# Tugas_Day_0-_Qurrata_Choir_Marham.net
KiCad netlist of a schematic drawn in EAGLE
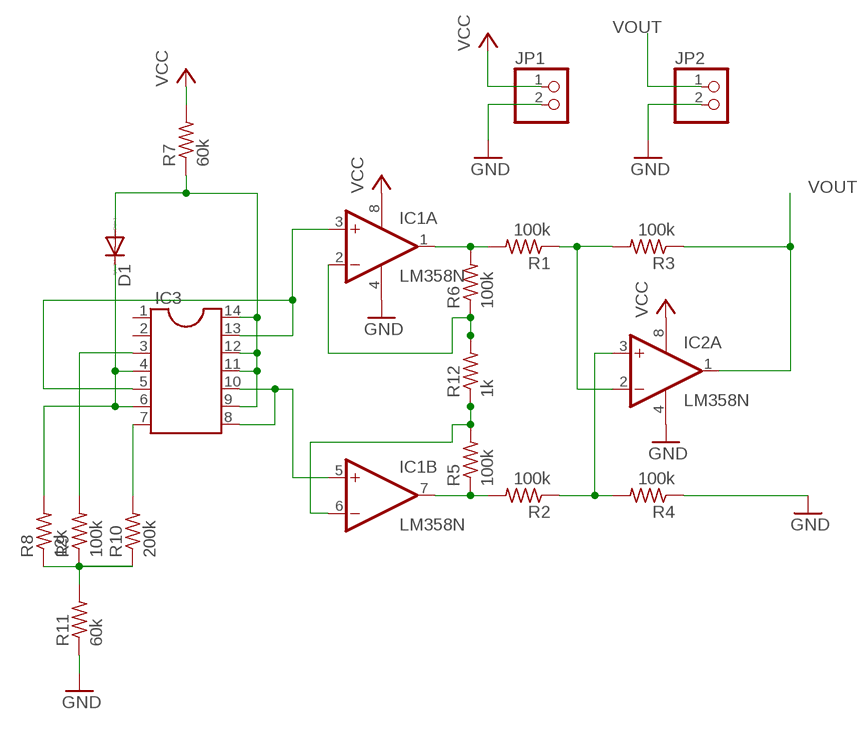
[diagram p0: schematic, sheet 1]

(export (version "E")
  (design (tool "Eeschema 10.0.6"))
  (components
    (comp (ref "D1")
      (value "DIODE-D-7.5")
      (footprint "eagle-import:D-7.5")
      (libsource (lib "eagle-import") (part "DIODE-D-7.5"))
    )
    (comp (ref "IC1")
      (value "LM358N")
      (footprint "eagle-import:DIL08")
      (libsource (lib "eagle-import") (part "LM358N"))
    )
    (comp (ref "IC2")
      (value "LM358N")
      (footprint "eagle-import:DIL08")
      (libsource (lib "eagle-import") (part "LM358N"))
    )
    (comp (ref "IC3")
      (value "DIL14")
      (footprint "eagle-import:DIL14")
      (libsource (lib "eagle-import") (part "DIL14"))
    )
    (comp (ref "JP1")
      (value "PINHD-1X2")
      (footprint "eagle-import:1X02")
      (libsource (lib "eagle-import") (part "PINHD-1X2"))
    )
    (comp (ref "JP2")
      (value "PINHD-1X2")
      (footprint "eagle-import:1X02")
      (libsource (lib "eagle-import") (part "PINHD-1X2"))
    )
    (comp (ref "R1")
      (value "100k")
      (footprint "eagle-import:0204_7")
      (libsource (lib "eagle-import") (part "R-US_0204/7"))
    )
    (comp (ref "R2")
      (value "100k")
      (footprint "eagle-import:0204_7")
      (libsource (lib "eagle-import") (part "R-US_0204/7"))
    )
    (comp (ref "R3")
      (value "100k")
      (footprint "eagle-import:0204_7")
      (libsource (lib "eagle-import") (part "R-US_0204/7"))
    )
    (comp (ref "R4")
      (value "100k")
      (footprint "eagle-import:0204_7")
      (libsource (lib "eagle-import") (part "R-US_0204/7"))
    )
    (comp (ref "R5")
      (value "100k")
      (footprint "eagle-import:0204_7")
      (libsource (lib "eagle-import") (part "R-US_0204/7"))
    )
    (comp (ref "R6")
      (value "100k")
      (footprint "eagle-import:0204_7")
      (libsource (lib "eagle-import") (part "R-US_0204/7"))
    )
    (comp (ref "R7")
      (value "60k")
      (footprint "eagle-import:0204_7")
      (libsource (lib "eagle-import") (part "R-US_0204/7"))
    )
    (comp (ref "R8")
      (value "12k")
      (footprint "eagle-import:0204_7")
      (libsource (lib "eagle-import") (part "R-US_0204/7"))
    )
    (comp (ref "R9")
      (value "100k")
      (footprint "eagle-import:0204_7")
      (libsource (lib "eagle-import") (part "R-US_0204/7"))
    )
    (comp (ref "R10")
      (value "200k")
      (footprint "eagle-import:0204_7")
      (libsource (lib "eagle-import") (part "R-US_0204/7"))
    )
    (comp (ref "R11")
      (value "60k")
      (footprint "eagle-import:0204_7")
      (libsource (lib "eagle-import") (part "R-US_0204/7"))
    )
    (comp (ref "R12")
      (value "1k")
      (footprint "eagle-import:0204_7")
      (libsource (lib "eagle-import") (part "R-US_0204/7"))
    )
  )
  (nets
    (net (code "1") (name "/VOUT") (class "Default")
      (node (ref "IC2") (pin "1") (pinfunction "OUT_1") (pintype "output"))
      (node (ref "JP2") (pin "1") (pinfunction "1_1") (pintype "passive"))
      (node (ref "R3") (pin "1") (pinfunction "1_1") (pintype "passive"))
    )
    (net (code "2") (name "GND") (class "Default")
      (node (ref "IC1") (pin "4") (pinfunction "V-_4") (pintype "power_in"))
      (node (ref "IC2") (pin "4") (pinfunction "V-_4") (pintype "power_in"))
      (node (ref "JP1") (pin "2") (pinfunction "2_2") (pintype "passive"))
      (node (ref "JP2") (pin "2") (pinfunction "2_2") (pintype "passive"))
      (node (ref "R11") (pin "1") (pinfunction "1_1") (pintype "passive"))
      (node (ref "R4") (pin "1") (pinfunction "1_1") (pintype "passive"))
    )
    (net (code "3") (name "Net-(D1-PadA)") (class "Default")
      (node (ref "D1") (pin "A") (pinfunction "A_A") (pintype "passive"))
      (node (ref "IC3") (pin "11") (pinfunction "11_11") (pintype "passive"))
      (node (ref "IC3") (pin "12") (pinfunction "12_12") (pintype "passive"))
      (node (ref "IC3") (pin "14") (pinfunction "14_14") (pintype "passive"))
      (node (ref "IC3") (pin "9") (pinfunction "9_9") (pintype "passive"))
      (node (ref "R7") (pin "1") (pinfunction "1_1") (pintype "passive"))
    )
    (net (code "4") (name "Net-(D1-PadC)") (class "Default")
      (node (ref "D1") (pin "C") (pinfunction "C_C") (pintype "passive"))
      (node (ref "IC3") (pin "4") (pinfunction "4_4") (pintype "passive"))
      (node (ref "IC3") (pin "6") (pinfunction "6_6") (pintype "passive"))
      (node (ref "R8") (pin "2") (pinfunction "2_2") (pintype "passive"))
    )
    (net (code "5") (name "Net-(IC1A-+IN)") (class "Default")
      (node (ref "IC1") (pin "3") (pinfunction "+IN_3") (pintype "input"))
      (node (ref "IC3") (pin "13") (pinfunction "13_13") (pintype "passive"))
      (node (ref "IC3") (pin "5") (pinfunction "5_5") (pintype "passive"))
    )
    (net (code "6") (name "Net-(IC1A--IN)") (class "Default")
      (node (ref "IC1") (pin "2") (pinfunction "-IN_2") (pintype "input"))
      (node (ref "R12") (pin "2") (pinfunction "2_2") (pintype "passive"))
      (node (ref "R6") (pin "1") (pinfunction "1_1") (pintype "passive"))
    )
    (net (code "7") (name "Net-(IC1A-OUT)") (class "Default")
      (node (ref "IC1") (pin "1") (pinfunction "OUT_1") (pintype "output"))
      (node (ref "R1") (pin "2") (pinfunction "2_2") (pintype "passive"))
      (node (ref "R6") (pin "2") (pinfunction "2_2") (pintype "passive"))
    )
    (net (code "8") (name "Net-(IC1B-+IN)") (class "Default")
      (node (ref "IC1") (pin "5") (pinfunction "+IN_5") (pintype "input"))
      (node (ref "IC3") (pin "10") (pinfunction "10_10") (pintype "passive"))
      (node (ref "IC3") (pin "8") (pinfunction "8_8") (pintype "passive"))
    )
    (net (code "9") (name "Net-(IC1B--IN)") (class "Default")
      (node (ref "IC1") (pin "6") (pinfunction "-IN_6") (pintype "input"))
      (node (ref "R12") (pin "1") (pinfunction "1_1") (pintype "passive"))
      (node (ref "R5") (pin "2") (pinfunction "2_2") (pintype "passive"))
    )
    (net (code "10") (name "Net-(IC1B-OUT)") (class "Default")
      (node (ref "IC1") (pin "7") (pinfunction "OUT_7") (pintype "output"))
      (node (ref "R2") (pin "2") (pinfunction "2_2") (pintype "passive"))
      (node (ref "R5") (pin "1") (pinfunction "1_1") (pintype "passive"))
    )
    (net (code "11") (name "Net-(IC2A-+IN)") (class "Default")
      (node (ref "IC2") (pin "3") (pinfunction "+IN_3") (pintype "input"))
      (node (ref "R2") (pin "1") (pinfunction "1_1") (pintype "passive"))
      (node (ref "R4") (pin "2") (pinfunction "2_2") (pintype "passive"))
    )
    (net (code "12") (name "Net-(IC2A--IN)") (class "Default")
      (node (ref "IC2") (pin "2") (pinfunction "-IN_2") (pintype "input"))
      (node (ref "R1") (pin "1") (pinfunction "1_1") (pintype "passive"))
      (node (ref "R3") (pin "2") (pinfunction "2_2") (pintype "passive"))
    )
    (net (code "13") (name "Net-(IC3-Pad3)") (class "Default")
      (node (ref "IC3") (pin "3") (pinfunction "3_3") (pintype "passive"))
      (node (ref "R9") (pin "2") (pinfunction "2_2") (pintype "passive"))
    )
    (net (code "14") (name "Net-(IC3-Pad7)") (class "Default")
      (node (ref "IC3") (pin "7") (pinfunction "7_7") (pintype "passive"))
      (node (ref "R10") (pin "2") (pinfunction "2_2") (pintype "passive"))
    )
    (net (code "15") (name "Net-(R10-Pad1)") (class "Default")
      (node (ref "R10") (pin "1") (pinfunction "1_1") (pintype "passive"))
      (node (ref "R11") (pin "2") (pinfunction "2_2") (pintype "passive"))
      (node (ref "R8") (pin "1") (pinfunction "1_1") (pintype "passive"))
      (node (ref "R9") (pin "1") (pinfunction "1_1") (pintype "passive"))
    )
    (net (code "16") (name "VCC") (class "Default")
      (node (ref "IC1") (pin "8") (pinfunction "V+_8") (pintype "power_in"))
      (node (ref "IC2") (pin "8") (pinfunction "V+_8") (pintype "power_in"))
      (node (ref "JP1") (pin "1") (pinfunction "1_1") (pintype "passive"))
      (node (ref "R7") (pin "2") (pinfunction "2_2") (pintype "passive"))
    )
    (net (code "17") (name "unconnected-(IC3-Pad1)") (class "Default")
      (node (ref "IC3") (pin "1") (pinfunction "1_1") (pintype "passive"))
    )
    (net (code "18") (name "unconnected-(IC3-Pad2)") (class "Default")
      (node (ref "IC3") (pin "2") (pinfunction "2_2") (pintype "passive"))
    )
  )
)
